# LPB-1.net
KiCad netlist of a schematic drawn in Altium Designer
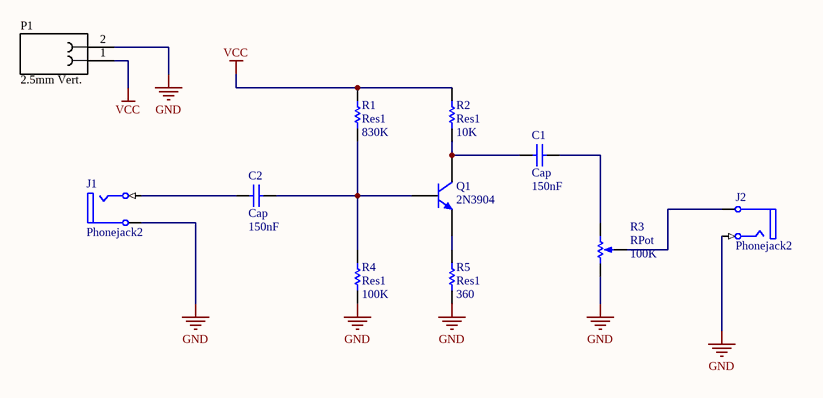
[diagram p0: LPB-1.SchDoc]

(export (version "E")
  (design (tool "Eeschema 10.0.6"))
  (components
    (comp (ref "C1")
      (value "Cap")
      (footprint "RAD-0.3")
      (description "Capacitor")
      (fields (field (name "ALTIUM_VALUE") "150nF") (field (name "PUBLISHER") "Altium Limited"))
      (libsource (lib "Miscellaneous Devices") (part "Cap"))
    )
    (comp (ref "C2")
      (value "Cap")
      (footprint "RAD-0.3")
      (description "Capacitor")
      (fields (field (name "ALTIUM_VALUE") "150nF") (field (name "PUBLISHER") "Altium Limited"))
      (libsource (lib "Miscellaneous Devices") (part "Cap"))
    )
    (comp (ref "J1")
      (value "Phonejack2")
      (footprint "JACK/6-V2")
      (description "Jack Socket, 1/4\" [6.5mm], Thru-Hole, Vertical, 2-Conductor Open Circuit")
      (fields (field (name "PUBLISHER") "Altium Limited"))
      (libsource (lib "Miscellaneous Connectors") (part "Phonejack2"))
    )
    (comp (ref "J2")
      (value "Phonejack2")
      (footprint "JACK/6-V2")
      (description "Jack Socket, 1/4\" [6.5mm], Thru-Hole, Vertical, 2-Conductor Open Circuit")
      (fields (field (name "PUBLISHER") "Altium Limited"))
      (libsource (lib "Miscellaneous Connectors") (part "Phonejack2"))
    )
    (comp (ref "P1")
      (value "2.5mm Vert.")
      (footprint "250-402/350-604_WAG")
      (description "PCB TERMINAL STRIPS FOR THR SOLDERING 250 SERIES")
      (libsource (lib "CON_PCB_250_2.5mm_WAG") (part "2P_250-402/350-604_WA"))
    )
    (comp (ref "Q1")
      (value "2N3904")
      (footprint "TO-92A")
      (description "NPN General Purpose Amplifier")
      (fields (field (name "PUBLISHER") "Altium Limited"))
      (libsource (lib "Miscellaneous Devices") (part "2N3904"))
    )
    (comp (ref "R1")
      (value "Res1")
      (footprint "AXIAL-0.3")
      (description "Resistor")
      (fields (field (name "ALTIUM_VALUE") "830K") (field (name "PUBLISHER") "Altium Limited"))
      (libsource (lib "Miscellaneous Devices") (part "Res1"))
    )
    (comp (ref "R2")
      (value "Res1")
      (footprint "AXIAL-0.3")
      (description "Resistor")
      (fields (field (name "ALTIUM_VALUE") "10K") (field (name "PUBLISHER") "Altium Limited"))
      (libsource (lib "Miscellaneous Devices") (part "Res1"))
    )
    (comp (ref "R3")
      (value "RPot")
      (footprint "VR5")
      (description "Potentiometer")
      (fields (field (name "ALTIUM_VALUE") "100K") (field (name "PUBLISHER") "Altium Limited"))
      (libsource (lib "Miscellaneous Devices") (part "RPot"))
    )
    (comp (ref "R4")
      (value "Res1")
      (footprint "AXIAL-0.3")
      (description "Resistor")
      (fields (field (name "ALTIUM_VALUE") "100K") (field (name "PUBLISHER") "Altium Limited"))
      (libsource (lib "Miscellaneous Devices") (part "Res1"))
    )
    (comp (ref "R5")
      (value "Res1")
      (footprint "AXIAL-0.3")
      (description "Resistor")
      (fields (field (name "ALTIUM_VALUE") "360") (field (name "PUBLISHER") "Altium Limited"))
      (libsource (lib "Miscellaneous Devices") (part "Res1"))
    )
  )
  (nets
    (net (code "1") (name "GND") (class "Default")
      (node (ref "J1") (pin "5") (pinfunction "S_5") (pintype "power_in"))
      (node (ref "J2") (pin "1") (pinfunction "T_1") (pintype "input"))
      (node (ref "P1") (pin "2") (pinfunction "2_2") (pintype "passive"))
      (node (ref "R3") (pin "1") (pinfunction "TOP_1") (pintype "passive"))
      (node (ref "R4") (pin "1") (pinfunction "1_1") (pintype "passive"))
      (node (ref "R5") (pin "1") (pinfunction "1_1") (pintype "passive"))
    )
    (net (code "2") (name "Net-(J1-T)") (class "Default")
      (node (ref "C2") (pin "1") (pinfunction "1_1") (pintype "passive"))
      (node (ref "J1") (pin "1") (pinfunction "T_1") (pintype "input"))
    )
    (net (code "3") (name "Net-(J2-S)") (class "Default")
      (node (ref "J2") (pin "5") (pinfunction "S_5") (pintype "power_in"))
      (node (ref "R3") (pin "3") (pinfunction "TAP_3") (pintype "passive"))
    )
    (net (code "4") (name "Net-(Q1-B)") (class "Default")
      (node (ref "C2") (pin "2") (pinfunction "2_2") (pintype "passive"))
      (node (ref "Q1") (pin "2") (pinfunction "B_2") (pintype "passive"))
      (node (ref "R1") (pin "1") (pinfunction "1_1") (pintype "passive"))
      (node (ref "R4") (pin "2") (pinfunction "2_2") (pintype "passive"))
    )
    (net (code "5") (name "Net-(Q1-C)") (class "Default")
      (node (ref "C1") (pin "1") (pinfunction "1_1") (pintype "passive"))
      (node (ref "Q1") (pin "3") (pinfunction "C_3") (pintype "passive"))
      (node (ref "R2") (pin "1") (pinfunction "1_1") (pintype "passive"))
    )
    (net (code "6") (name "Net-(Q1-E)") (class "Default")
      (node (ref "Q1") (pin "1") (pinfunction "E_1") (pintype "passive"))
      (node (ref "R5") (pin "2") (pinfunction "2_2") (pintype "passive"))
    )
    (net (code "7") (name "Net-(R3-BOT)") (class "Default")
      (node (ref "C1") (pin "2") (pinfunction "2_2") (pintype "passive"))
      (node (ref "R3") (pin "2") (pinfunction "BOT_2") (pintype "passive"))
    )
    (net (code "8") (name "VCC") (class "Default")
      (node (ref "P1") (pin "1") (pinfunction "1_1") (pintype "passive"))
      (node (ref "R1") (pin "2") (pinfunction "2_2") (pintype "passive"))
      (node (ref "R2") (pin "2") (pinfunction "2_2") (pintype "passive"))
    )
  )
)
